# JTAG10M-STLV2.net
KiCad netlist of a schematic drawn in EAGLE
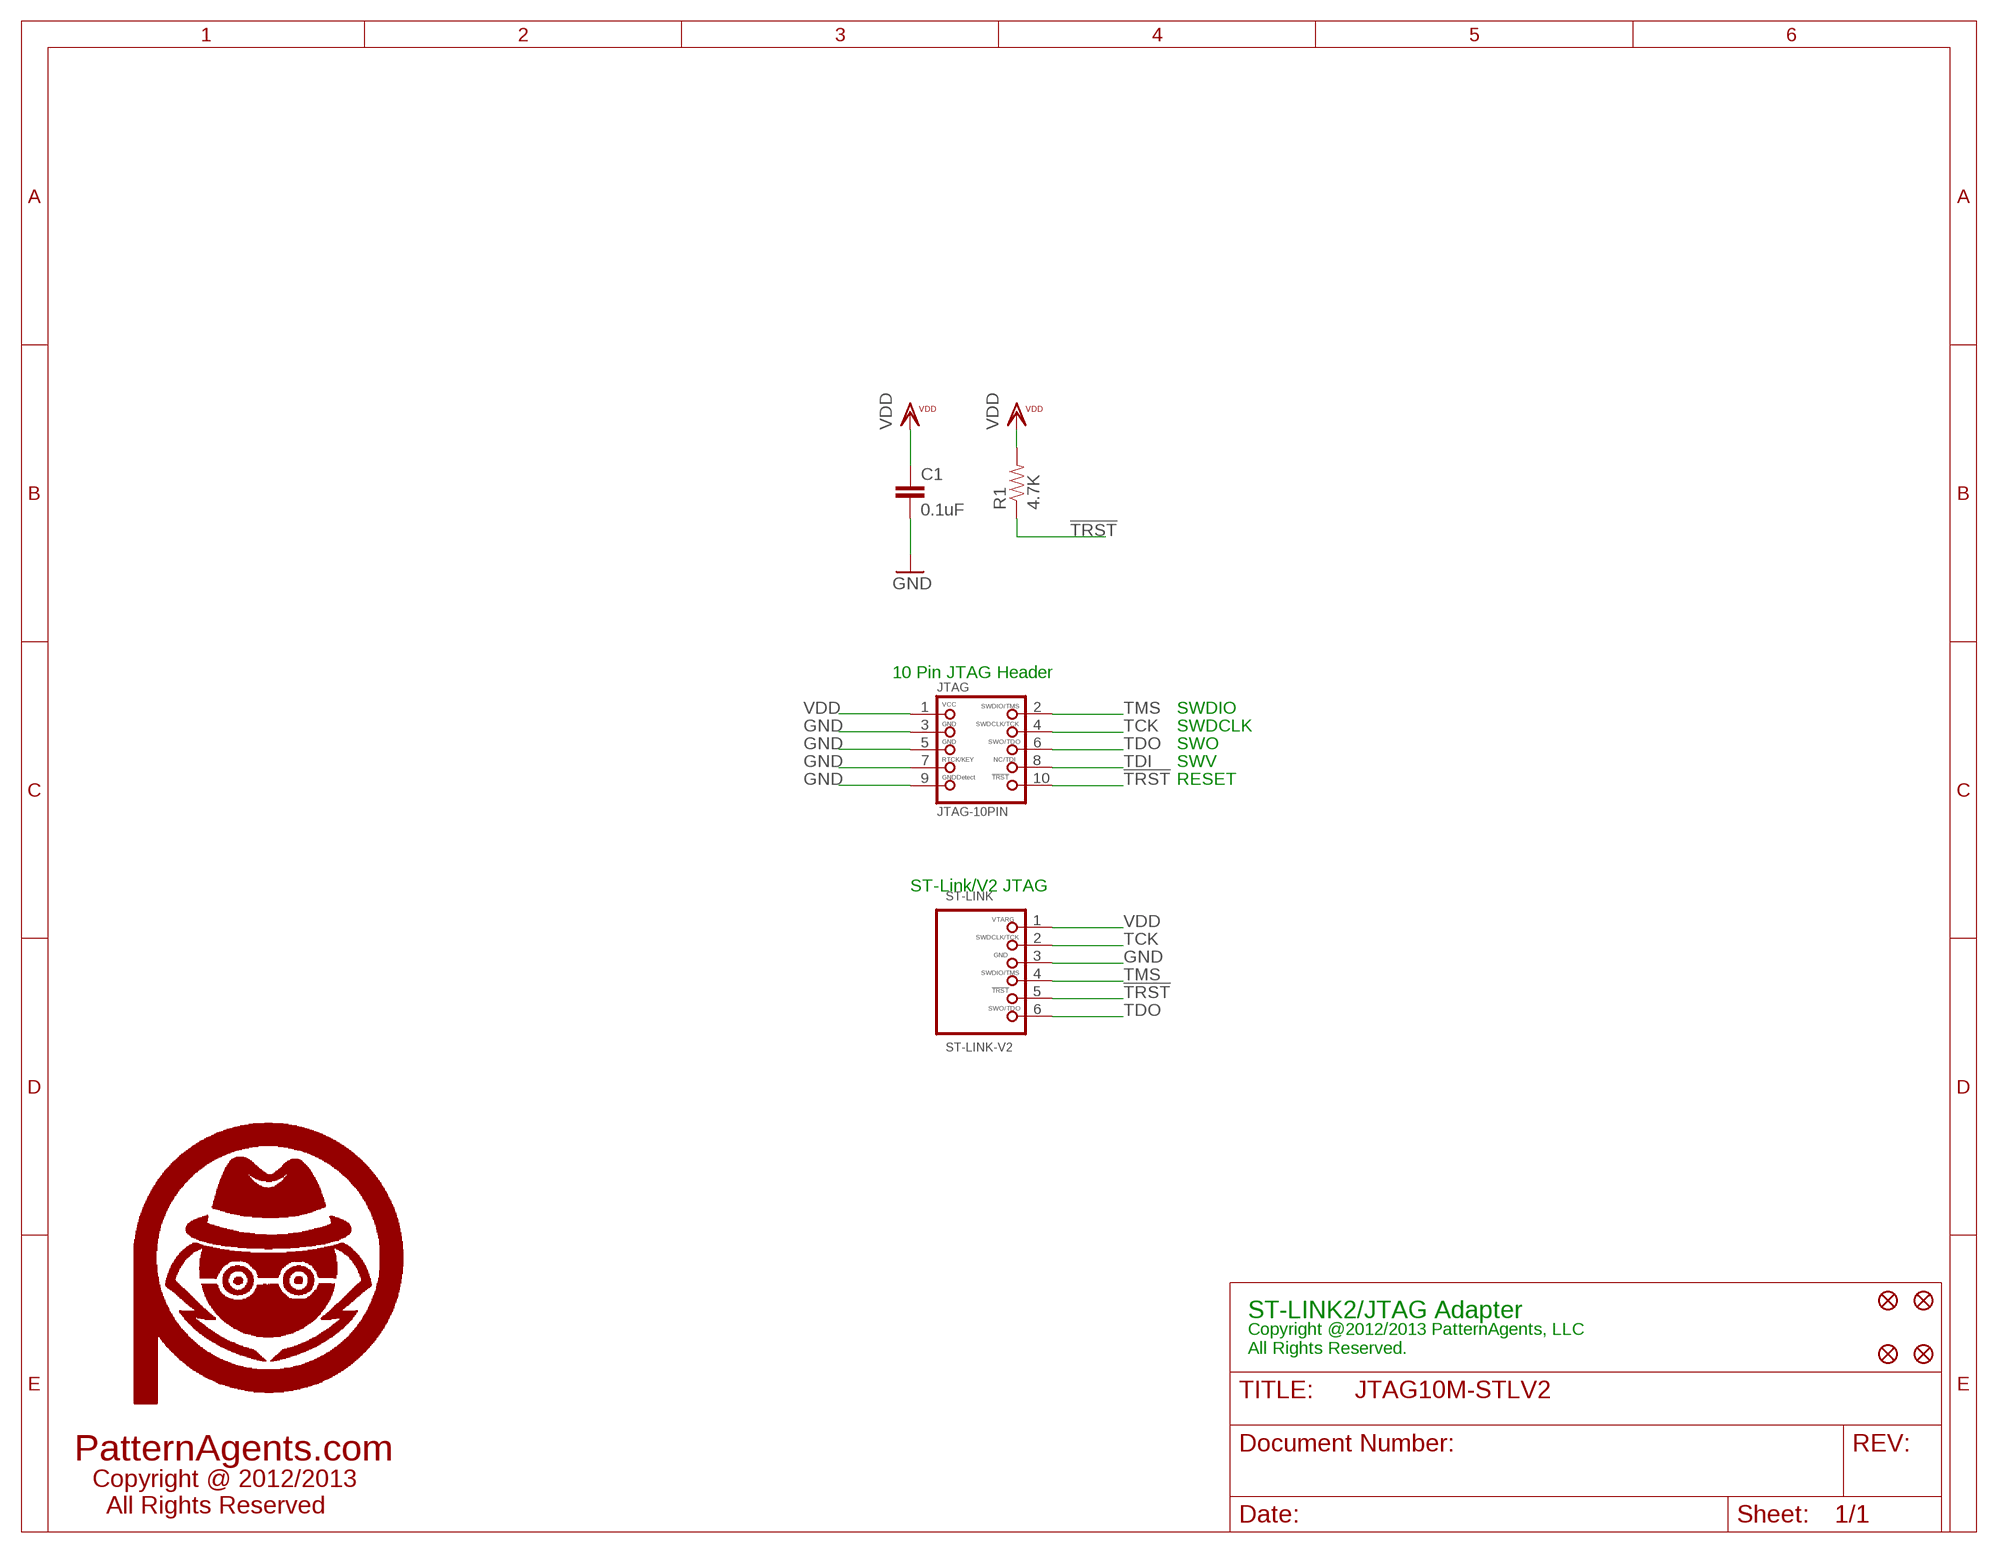
[diagram p0: schematic, sheet 1]

(export (version "E")
  (design (tool "Eeschema 10.0.6"))
  (components
    (comp (ref "C1")
      (value "0.1uF")
      (footprint "eagle-import:0603-CAP")
      (libsource (lib "eagle-import") (part "CAP0603-CAP"))
    )
    (comp (ref "FID1")
      (value "FIDUCIAL1.5X3")
      (footprint "eagle-import:FIDUCIAL-1.5X3")
      (libsource (lib "eagle-import") (part "FIDUCIAL1.5X3"))
    )
    (comp (ref "FID2")
      (value "FIDUCIAL1.5X3")
      (footprint "eagle-import:FIDUCIAL-1.5X3")
      (libsource (lib "eagle-import") (part "FIDUCIAL1.5X3"))
    )
    (comp (ref "FID3")
      (value "FIDUCIAL1.5X3")
      (footprint "eagle-import:FIDUCIAL-1.5X3")
      (libsource (lib "eagle-import") (part "FIDUCIAL1.5X3"))
    )
    (comp (ref "FID4")
      (value "FIDUCIAL1.5X3")
      (footprint "eagle-import:FIDUCIAL-1.5X3")
      (libsource (lib "eagle-import") (part "FIDUCIAL1.5X3"))
    )
    (comp (ref "JTAG")
      (value "JTAG-10PIN")
      (footprint "eagle-import:2X05_1.27MM_SMT")
      (libsource (lib "eagle-import") (part "JTAG-10PINSMD"))
    )
    (comp (ref "R1")
      (value "4.7K")
      (footprint "eagle-import:0603-RES")
      (libsource (lib "eagle-import") (part "RESISTOR_SFE0603-RES"))
    )
    (comp (ref "ST-LINK")
      (value "ST-LINK-V2")
      (footprint "eagle-import:1X06_2.54MM_PTH")
      (libsource (lib "eagle-import") (part "ST-LINK-V2"))
    )
    (comp (ref "U$2")
      (value "PA_LOGO_SYMLARGE")
      (footprint "eagle-import:PA_LOGO_AGENT_LRG_SYM")
      (libsource (lib "eagle-import") (part "PA_LOGO_SYMLARGE"))
    )
  )
  (nets
    (net (code "1") (name "/TCK") (class "Default")
      (node (ref "JTAG") (pin "4") (pinfunction "4_4") (pintype "passive"))
      (node (ref "ST-LINK") (pin "2") (pinfunction "2_2") (pintype "passive"))
    )
    (net (code "2") (name "/TDI") (class "Default")
      (node (ref "JTAG") (pin "8") (pinfunction "8_8") (pintype "passive"))
    )
    (net (code "3") (name "/TDO") (class "Default")
      (node (ref "JTAG") (pin "6") (pinfunction "6_6") (pintype "passive"))
      (node (ref "ST-LINK") (pin "6") (pinfunction "6_6") (pintype "passive"))
    )
    (net (code "4") (name "/TMS") (class "Default")
      (node (ref "JTAG") (pin "2") (pinfunction "2_2") (pintype "passive"))
      (node (ref "ST-LINK") (pin "4") (pinfunction "4_4") (pintype "passive"))
    )
    (net (code "5") (name "/~{TRST}") (class "Default")
      (node (ref "JTAG") (pin "10") (pinfunction "10_10") (pintype "passive"))
      (node (ref "R1") (pin "1") (pinfunction "1_1") (pintype "passive"))
      (node (ref "ST-LINK") (pin "5") (pinfunction "5_5") (pintype "passive"))
    )
    (net (code "6") (name "GND") (class "Default")
      (node (ref "C1") (pin "2") (pinfunction "2_2") (pintype "passive"))
      (node (ref "JTAG") (pin "3") (pinfunction "3_3") (pintype "passive"))
      (node (ref "JTAG") (pin "5") (pinfunction "5_5") (pintype "passive"))
      (node (ref "JTAG") (pin "7") (pinfunction "7_7") (pintype "passive"))
      (node (ref "JTAG") (pin "9") (pinfunction "9_9") (pintype "passive"))
      (node (ref "ST-LINK") (pin "3") (pinfunction "3_3") (pintype "passive"))
    )
    (net (code "7") (name "VDD") (class "Default")
      (node (ref "C1") (pin "1") (pinfunction "1_1") (pintype "passive"))
      (node (ref "JTAG") (pin "1") (pinfunction "1_1") (pintype "passive"))
      (node (ref "R1") (pin "2") (pinfunction "2_2") (pintype "passive"))
      (node (ref "ST-LINK") (pin "1") (pinfunction "1_1") (pintype "passive"))
    )
  )
)
